# Patch_panel_module_-_Insert.net
KiCad netlist of a schematic drawn in EAGLE
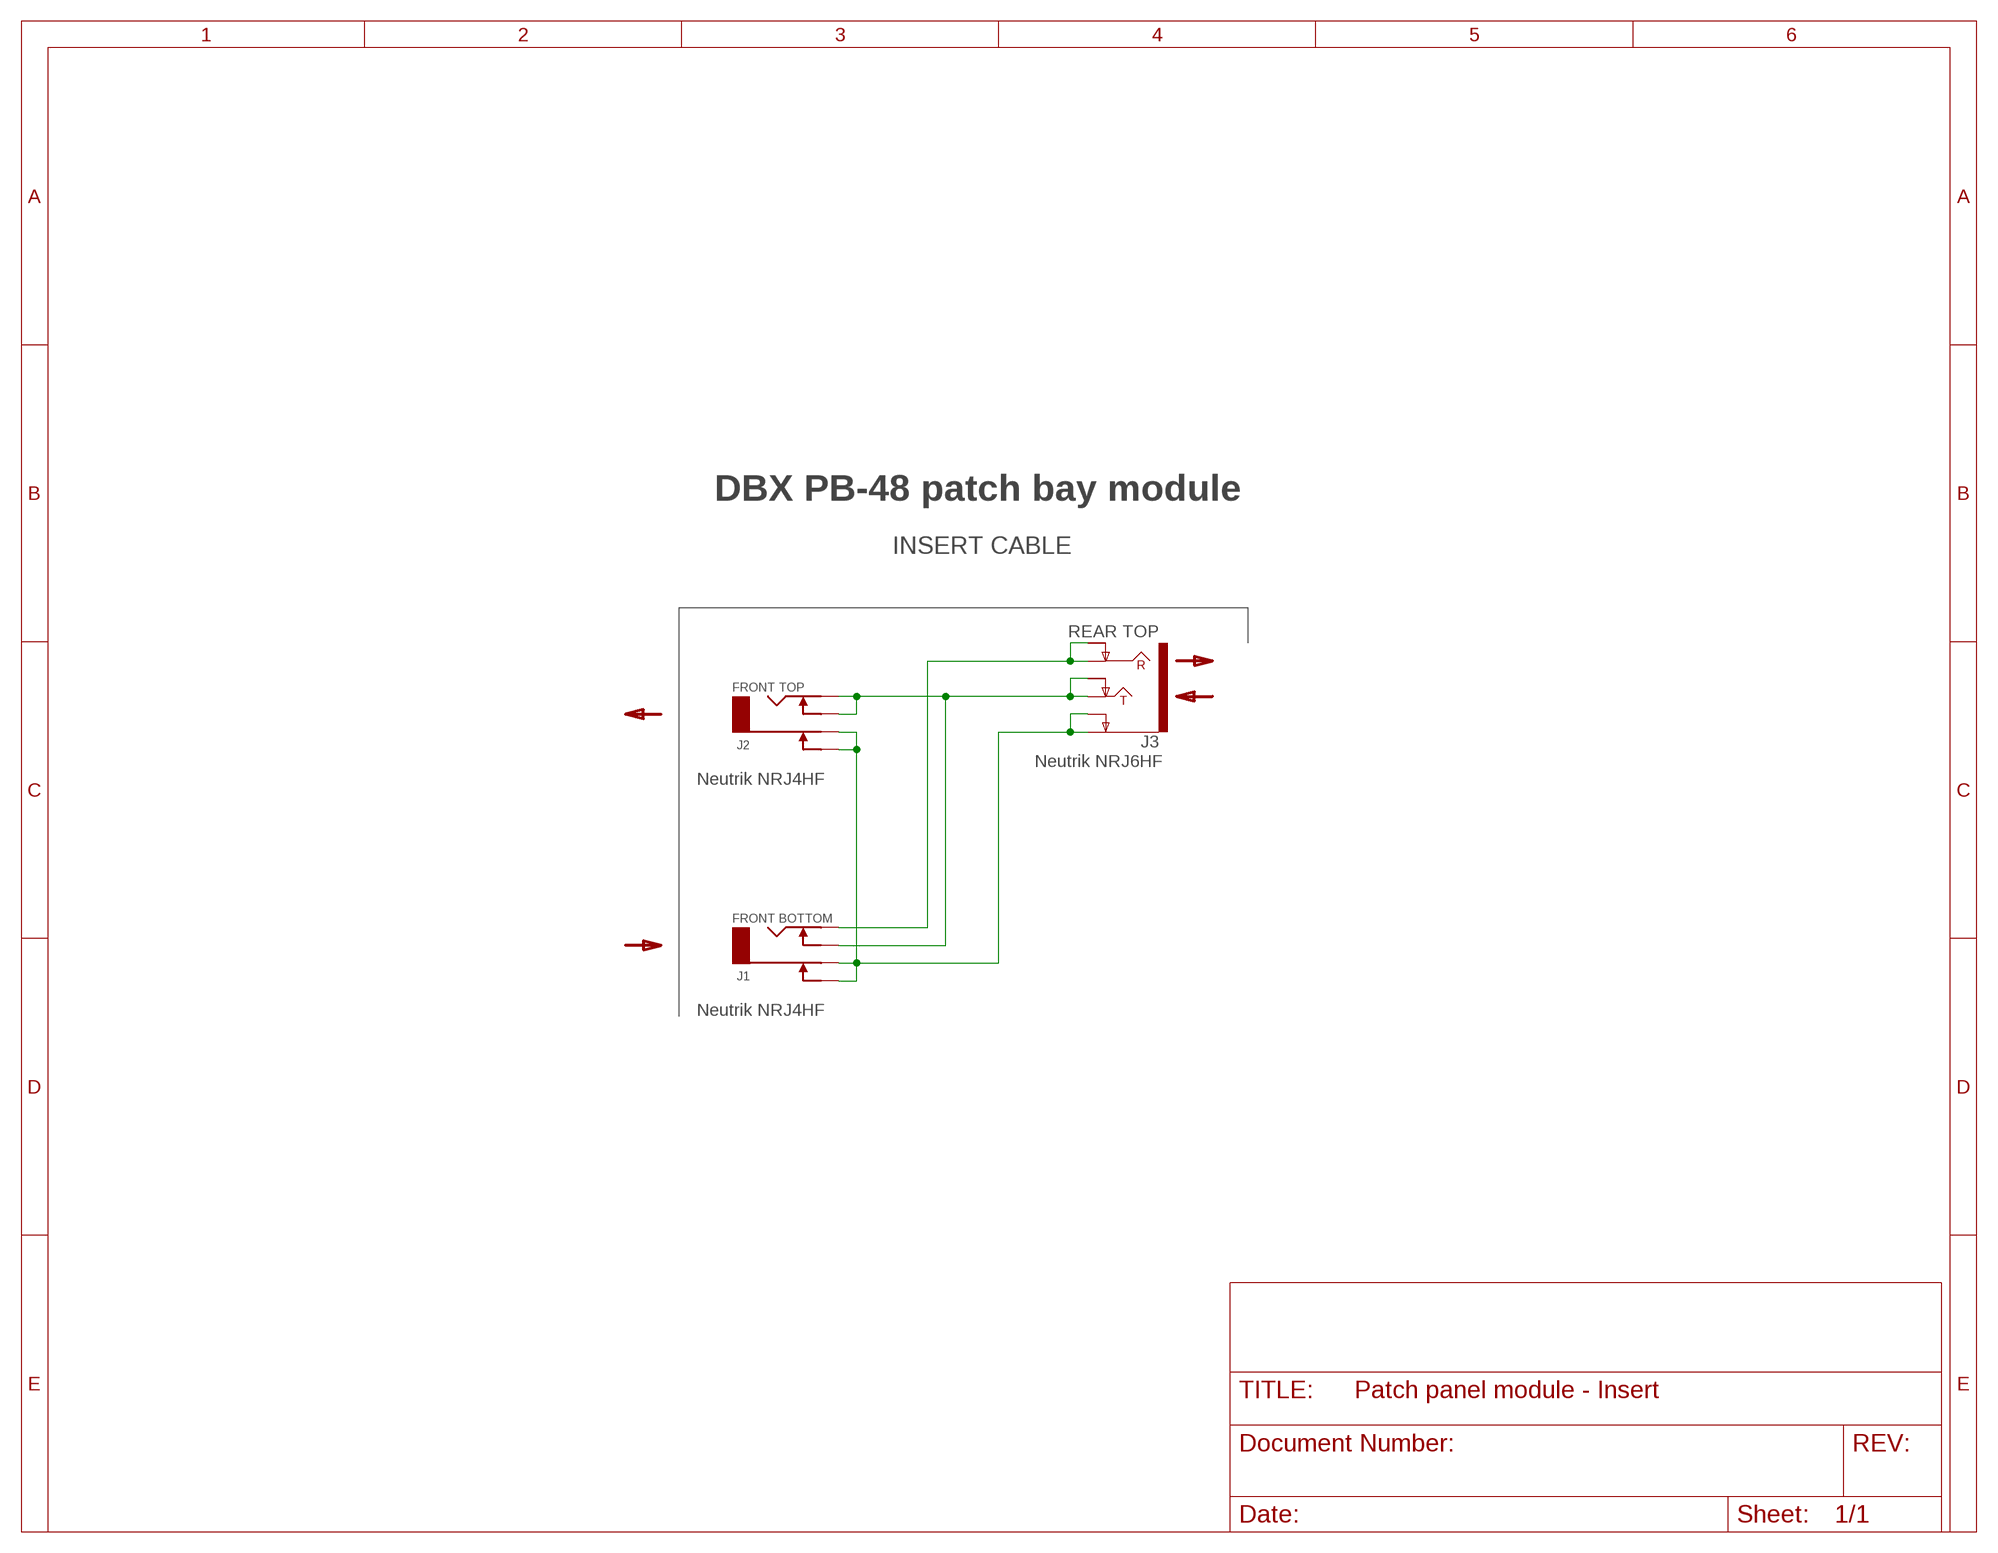
[diagram p0: schematic, sheet 1]

(export (version "E")
  (design (tool "Eeschema 10.0.6"))
  (components
    (comp (ref "J1")
      (value "FRONT BOTTOM")
      (footprint "eagle-import:NEUTRIK-NRJ4HF")
      (libsource (lib "eagle-import") (part "JACK-TS-SW-2X"))
    )
    (comp (ref "J2")
      (value "FRONT TOP")
      (footprint "eagle-import:NEUTRIK-NRJ4HF")
      (libsource (lib "eagle-import") (part "JACK-TS-SW-2X"))
    )
    (comp (ref "J3")
      (value "REAR TOP")
      (footprint "eagle-import:NEUTRIK-NRJ6HF")
      (libsource (lib "eagle-import") (part "AUDIO_JACK_TRS_0.25{dblquote}_PTH_RA-NRJ6HM"))
    )
  )
  (nets
    (net (code "1") (name "Net-(J1-SLEEVE)") (class "Default")
      (node (ref "J1") (pin "S") (pinfunction "SLEEVE_S") (pintype "bidirectional"))
      (node (ref "J1") (pin "SN") (pinfunction "SN_SN") (pintype "bidirectional"))
      (node (ref "J2") (pin "S") (pinfunction "SLEEVE_S") (pintype "bidirectional"))
      (node (ref "J2") (pin "SN") (pinfunction "SN_SN") (pintype "bidirectional"))
      (node (ref "J3") (pin "S") (pinfunction "EARTH_S") (pintype "bidirectional"))
      (node (ref "J3") (pin "SN") (pinfunction "EARTH-NORM_SN") (pintype "bidirectional"))
    )
    (net (code "2") (name "Net-(J1-TIP)") (class "Default")
      (node (ref "J1") (pin "T") (pinfunction "TIP_T") (pintype "bidirectional"))
      (node (ref "J3") (pin "R") (pinfunction "RING_R") (pintype "bidirectional"))
      (node (ref "J3") (pin "RN") (pinfunction "RING-NORM_RN") (pintype "bidirectional"))
    )
    (net (code "3") (name "Net-(J2-TIP)") (class "Default")
      (node (ref "J1") (pin "TN") (pinfunction "TN_TN") (pintype "bidirectional"))
      (node (ref "J2") (pin "T") (pinfunction "TIP_T") (pintype "bidirectional"))
      (node (ref "J2") (pin "TN") (pinfunction "TN_TN") (pintype "bidirectional"))
      (node (ref "J3") (pin "T") (pinfunction "TIP_T") (pintype "bidirectional"))
      (node (ref "J3") (pin "TN") (pinfunction "TIP-NORM_TN") (pintype "bidirectional"))
    )
  )
)
